# bh_ai8_di8_alph.net
KiCad netlist of a schematic drawn in Altium Designer
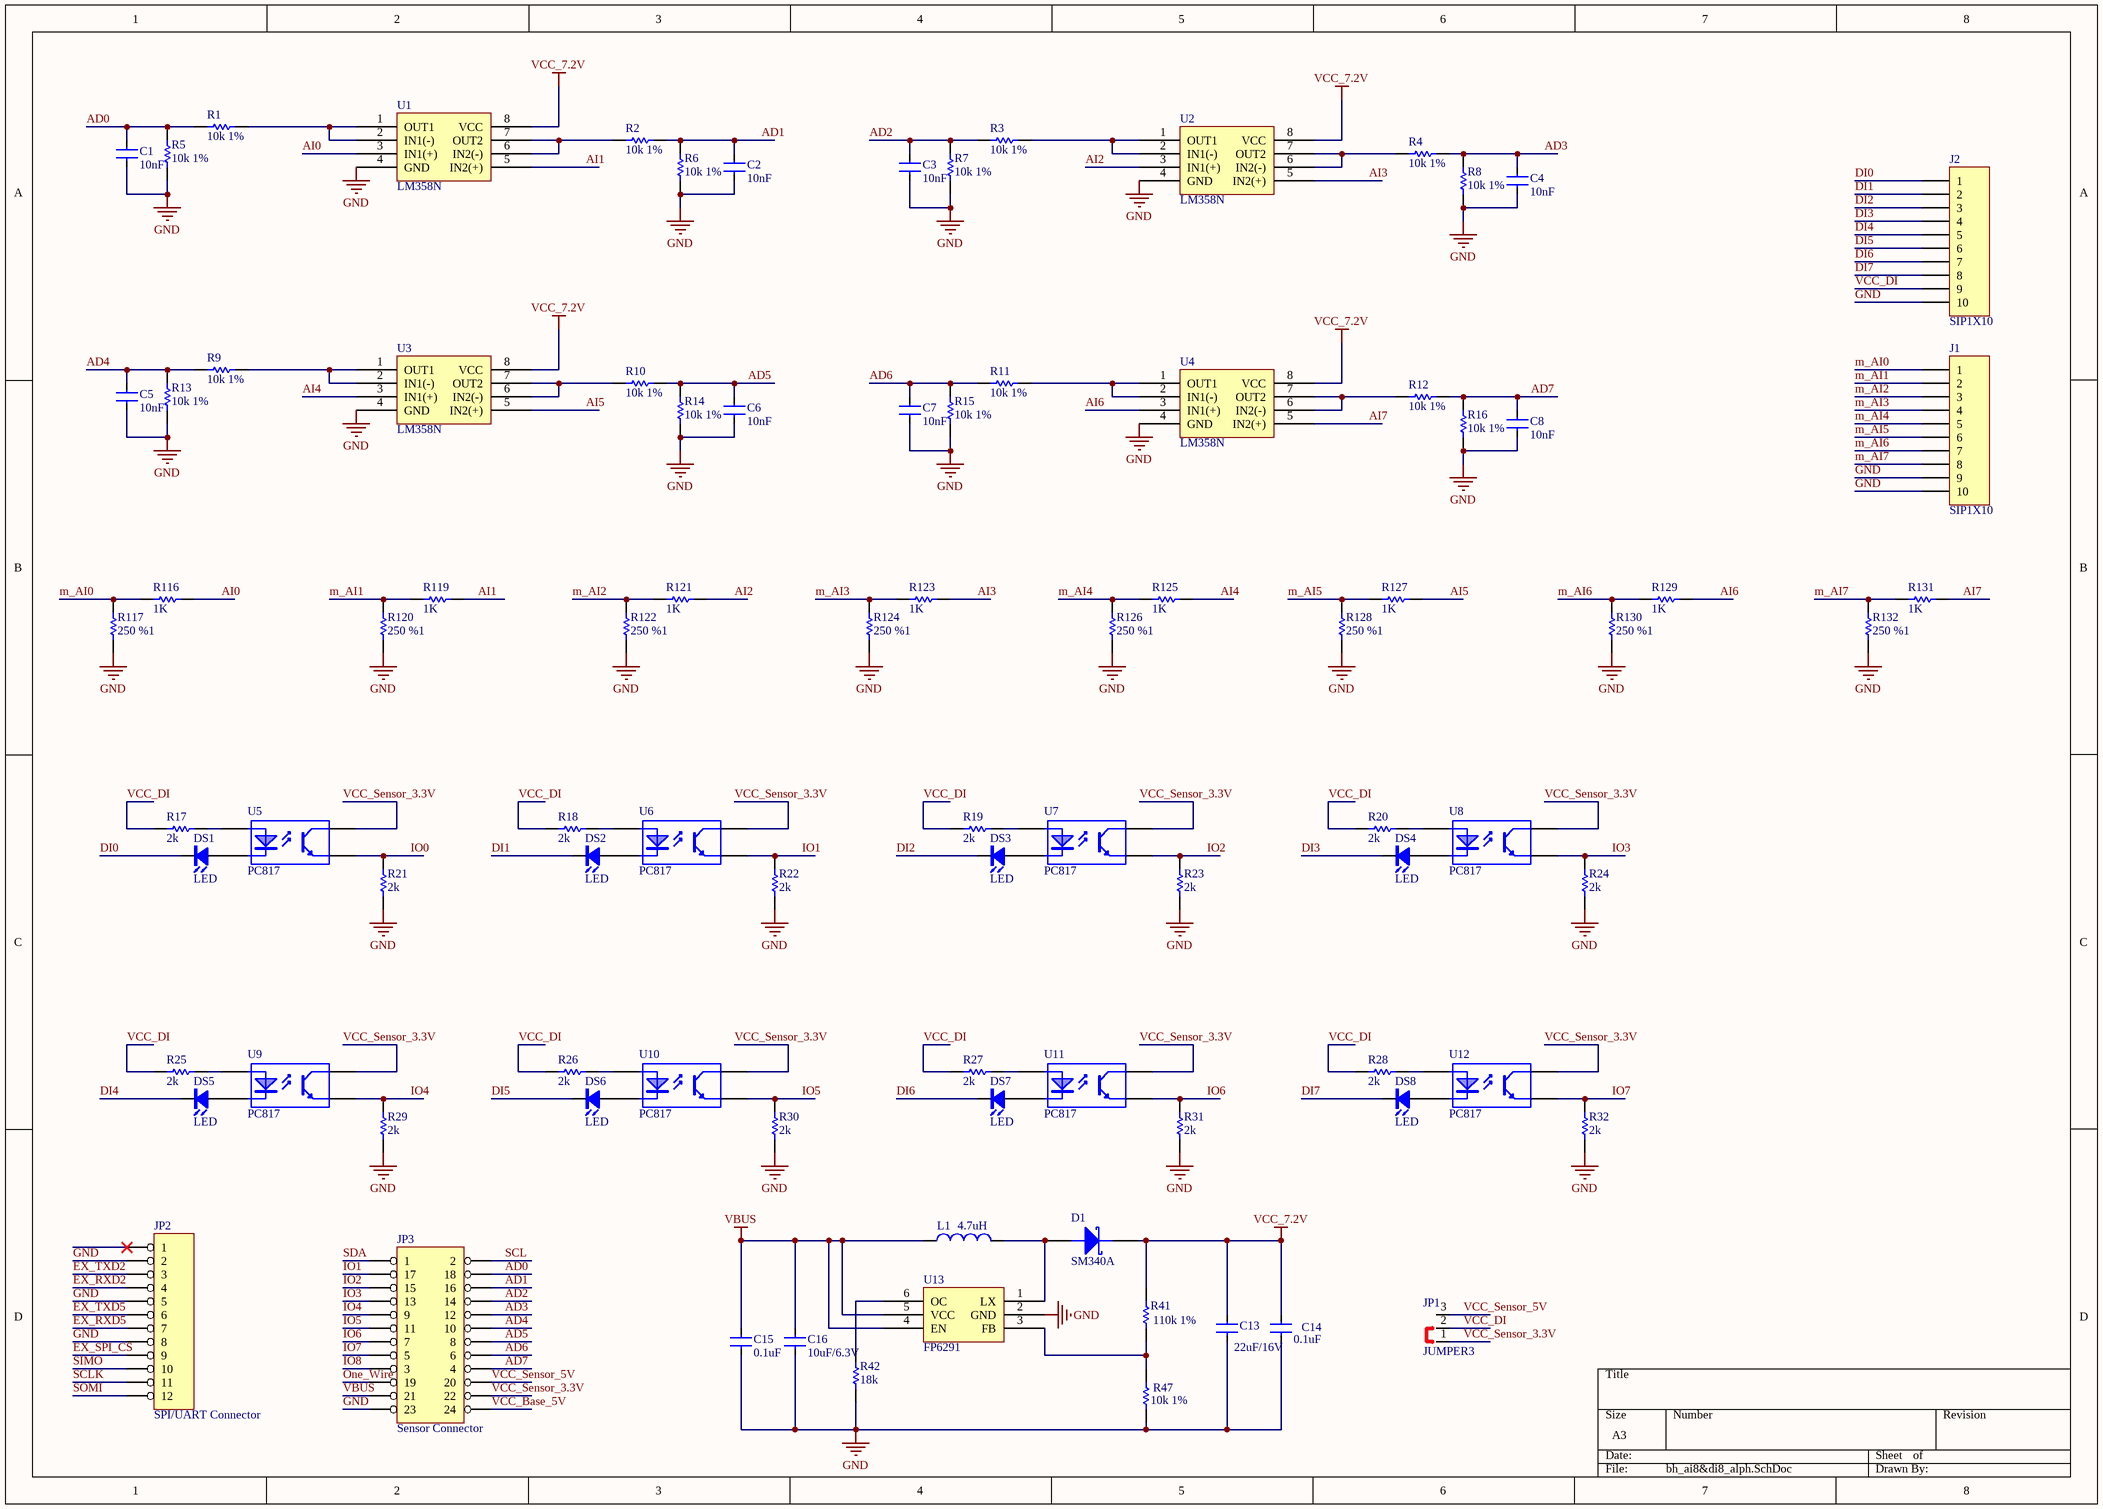
[diagram p0: bh_ai8&di8_alph.SchDoc]

(export (version "E")
  (design (tool "Eeschema 10.0.6"))
  (components
    (comp (ref "C1")
      (value "10nF")
      (footprint "C0603")
      (description "SMD-CAP")
      (libsource (lib "BH_DESIGN_DEVICE") (part "CAP-SMD"))
    )
    (comp (ref "C2")
      (value "10nF")
      (footprint "C0603")
      (description "SMD-CAP")
      (libsource (lib "BH_DESIGN_DEVICE") (part "CAP-SMD"))
    )
    (comp (ref "C3")
      (value "10nF")
      (footprint "C0603")
      (description "SMD-CAP")
      (libsource (lib "BH_DESIGN_DEVICE") (part "CAP-SMD"))
    )
    (comp (ref "C4")
      (value "10nF")
      (footprint "C0603")
      (description "SMD-CAP")
      (libsource (lib "BH_DESIGN_DEVICE") (part "CAP-SMD"))
    )
    (comp (ref "C5")
      (value "10nF")
      (footprint "C0603")
      (description "SMD-CAP")
      (libsource (lib "BH_DESIGN_DEVICE") (part "CAP-SMD"))
    )
    (comp (ref "C6")
      (value "10nF")
      (footprint "C0603")
      (description "SMD-CAP")
      (libsource (lib "BH_DESIGN_DEVICE") (part "CAP-SMD"))
    )
    (comp (ref "C7")
      (value "10nF")
      (footprint "C0603")
      (description "SMD-CAP")
      (libsource (lib "BH_DESIGN_DEVICE") (part "CAP-SMD"))
    )
    (comp (ref "C8")
      (value "10nF")
      (footprint "C0603")
      (description "SMD-CAP")
      (libsource (lib "BH_DESIGN_DEVICE") (part "CAP-SMD"))
    )
    (comp (ref "C13")
      (value "22uF/16V")
      (footprint "C0805")
      (description "SMD-CAP")
      (libsource (lib "5D_DEVICE") (part "CAP-SMD"))
    )
    (comp (ref "C14")
      (value "0.1uF")
      (footprint "C0603")
      (description "SMD-CAP")
      (libsource (lib "5D_DEVICE") (part "CAP-SMD"))
    )
    (comp (ref "C15")
      (value "0.1uF")
      (footprint "C0603")
      (description "SMD-CAP")
      (libsource (lib "5D_DEVICE") (part "CAP-SMD"))
    )
    (comp (ref "C16")
      (value "10uF/6.3V")
      (footprint "C0805")
      (description "SMD-CAP")
      (libsource (lib "5D_DEVICE") (part "CAP-SMD"))
    )
    (comp (ref "D1")
      (value "SM340A")
      (footprint "DO-214")
      (description "Schottky Diode")
      (libsource (lib "5D_DEVICE") (part "DIODE SCHOTTKY"))
    )
    (comp (ref "DS1") (value "LED") (footprint "D0805") (libsource (lib "BH_DESIGN_DEVICE") (part "LED")))
    (comp (ref "DS2") (value "LED") (footprint "D0805") (libsource (lib "BH_DESIGN_DEVICE") (part "LED")))
    (comp (ref "DS3") (value "LED") (footprint "D0805") (libsource (lib "BH_DESIGN_DEVICE") (part "LED")))
    (comp (ref "DS4") (value "LED") (footprint "D0805") (libsource (lib "BH_DESIGN_DEVICE") (part "LED")))
    (comp (ref "DS5") (value "LED") (footprint "D0805") (libsource (lib "BH_DESIGN_DEVICE") (part "LED")))
    (comp (ref "DS6") (value "LED") (footprint "D0805") (libsource (lib "BH_DESIGN_DEVICE") (part "LED")))
    (comp (ref "DS7") (value "LED") (footprint "D0805") (libsource (lib "BH_DESIGN_DEVICE") (part "LED")))
    (comp (ref "DS8") (value "LED") (footprint "D0805") (libsource (lib "BH_DESIGN_DEVICE") (part "LED")))
    (comp (ref "J1")
      (value "SIP1X10")
      (footprint "CON10*0.381")
      (description "Connector")
      (libsource (lib "BH_DESIGN_CONNECTOR") (part "SIP1X10"))
    )
    (comp (ref "J2")
      (value "SIP1X10")
      (footprint "CON10*0.381")
      (description "Connector")
      (libsource (lib "BH_DESIGN_CONNECTOR") (part "SIP1X10"))
    )
    (comp (ref "JP1")
      (value "JUMPER3")
      (footprint "SIP1X3X2.54")
      (description "Jumper")
      (libsource (lib "BH_DESIGN_CONNECTOR") (part "JUMPER3"))
    )
    (comp (ref "JP2")
      (value "SPI/UART Connector")
      (footprint "SIP1x12x2.54")
      (description "单排排针直角")
      (libsource (lib "5D_CONNECTOR") (part "SIP1X12"))
    )
    (comp (ref "JP3")
      (value "Sensor Connector")
      (footprint "SIP2X12X2.54")
      (description "双排排针直角")
      (libsource (lib "5D_CONNECTOR") (part "SIP2X12"))
    )
    (comp (ref "L1")
      (value "4.7uH")
      (footprint "R1206")
      (description "Inductor")
      (libsource (lib "5D_DEVICE") (part "INDUCTOR"))
    )
    (comp (ref "R1")
      (value "10k 1%")
      (footprint "R0603")
      (description "Resistor")
      (libsource (lib "BH_DESIGN_DEVICE") (part "RES"))
    )
    (comp (ref "R2")
      (value "10k 1%")
      (footprint "R0603")
      (description "Resistor")
      (libsource (lib "BH_DESIGN_DEVICE") (part "RES"))
    )
    (comp (ref "R3")
      (value "10k 1%")
      (footprint "R0603")
      (description "Resistor")
      (libsource (lib "BH_DESIGN_DEVICE") (part "RES"))
    )
    (comp (ref "R4")
      (value "10k 1%")
      (footprint "R0603")
      (description "Resistor")
      (libsource (lib "BH_DESIGN_DEVICE") (part "RES"))
    )
    (comp (ref "R5")
      (value "10k 1%")
      (footprint "R0603")
      (description "Resistor")
      (libsource (lib "BH_DESIGN_DEVICE") (part "RES"))
    )
    (comp (ref "R6")
      (value "10k 1%")
      (footprint "R0603")
      (description "Resistor")
      (libsource (lib "BH_DESIGN_DEVICE") (part "RES"))
    )
    (comp (ref "R7")
      (value "10k 1%")
      (footprint "R0603")
      (description "Resistor")
      (libsource (lib "BH_DESIGN_DEVICE") (part "RES"))
    )
    (comp (ref "R8")
      (value "10k 1%")
      (footprint "R0603")
      (description "Resistor")
      (libsource (lib "BH_DESIGN_DEVICE") (part "RES"))
    )
    (comp (ref "R9")
      (value "10k 1%")
      (footprint "R0603")
      (description "Resistor")
      (libsource (lib "BH_DESIGN_DEVICE") (part "RES"))
    )
    (comp (ref "R10")
      (value "10k 1%")
      (footprint "R0603")
      (description "Resistor")
      (libsource (lib "BH_DESIGN_DEVICE") (part "RES"))
    )
    (comp (ref "R11")
      (value "10k 1%")
      (footprint "R0603")
      (description "Resistor")
      (libsource (lib "BH_DESIGN_DEVICE") (part "RES"))
    )
    (comp (ref "R12")
      (value "10k 1%")
      (footprint "R0603")
      (description "Resistor")
      (libsource (lib "BH_DESIGN_DEVICE") (part "RES"))
    )
    (comp (ref "R13")
      (value "10k 1%")
      (footprint "R0603")
      (description "Resistor")
      (libsource (lib "BH_DESIGN_DEVICE") (part "RES"))
    )
    (comp (ref "R14")
      (value "10k 1%")
      (footprint "R0603")
      (description "Resistor")
      (libsource (lib "BH_DESIGN_DEVICE") (part "RES"))
    )
    (comp (ref "R15")
      (value "10k 1%")
      (footprint "R0603")
      (description "Resistor")
      (libsource (lib "BH_DESIGN_DEVICE") (part "RES"))
    )
    (comp (ref "R16")
      (value "10k 1%")
      (footprint "R0603")
      (description "Resistor")
      (libsource (lib "BH_DESIGN_DEVICE") (part "RES"))
    )
    (comp (ref "R17")
      (value "2k")
      (footprint "R0603")
      (description "Resistor")
      (libsource (lib "BH_DESIGN_DEVICE") (part "RES"))
    )
    (comp (ref "R18")
      (value "2k")
      (footprint "R0603")
      (description "Resistor")
      (libsource (lib "BH_DESIGN_DEVICE") (part "RES"))
    )
    (comp (ref "R19")
      (value "2k")
      (footprint "R0603")
      (description "Resistor")
      (libsource (lib "BH_DESIGN_DEVICE") (part "RES"))
    )
    (comp (ref "R20")
      (value "2k")
      (footprint "R0603")
      (description "Resistor")
      (libsource (lib "BH_DESIGN_DEVICE") (part "RES"))
    )
    (comp (ref "R21")
      (value "2k")
      (footprint "R0603")
      (description "Resistor")
      (libsource (lib "BH_DESIGN_DEVICE") (part "RES"))
    )
    (comp (ref "R22")
      (value "2k")
      (footprint "R0603")
      (description "Resistor")
      (libsource (lib "BH_DESIGN_DEVICE") (part "RES"))
    )
    (comp (ref "R23")
      (value "2k")
      (footprint "R0603")
      (description "Resistor")
      (libsource (lib "BH_DESIGN_DEVICE") (part "RES"))
    )
    (comp (ref "R24")
      (value "2k")
      (footprint "R0603")
      (description "Resistor")
      (libsource (lib "BH_DESIGN_DEVICE") (part "RES"))
    )
    (comp (ref "R25")
      (value "2k")
      (footprint "R0603")
      (description "Resistor")
      (libsource (lib "BH_DESIGN_DEVICE") (part "RES"))
    )
    (comp (ref "R26")
      (value "2k")
      (footprint "R0603")
      (description "Resistor")
      (libsource (lib "BH_DESIGN_DEVICE") (part "RES"))
    )
    (comp (ref "R27")
      (value "2k")
      (footprint "R0603")
      (description "Resistor")
      (libsource (lib "BH_DESIGN_DEVICE") (part "RES"))
    )
    (comp (ref "R28")
      (value "2k")
      (footprint "R0603")
      (description "Resistor")
      (libsource (lib "BH_DESIGN_DEVICE") (part "RES"))
    )
    (comp (ref "R29")
      (value "2k")
      (footprint "R0603")
      (description "Resistor")
      (libsource (lib "BH_DESIGN_DEVICE") (part "RES"))
    )
    (comp (ref "R30")
      (value "2k")
      (footprint "R0603")
      (description "Resistor")
      (libsource (lib "BH_DESIGN_DEVICE") (part "RES"))
    )
    (comp (ref "R31")
      (value "2k")
      (footprint "R0603")
      (description "Resistor")
      (libsource (lib "BH_DESIGN_DEVICE") (part "RES"))
    )
    (comp (ref "R32")
      (value "2k")
      (footprint "R0603")
      (description "Resistor")
      (libsource (lib "BH_DESIGN_DEVICE") (part "RES"))
    )
    (comp (ref "R41")
      (value "110k 1%")
      (footprint "R0603")
      (description "Resistor")
      (libsource (lib "5D_DEVICE") (part "RES"))
    )
    (comp (ref "R42")
      (value "18k")
      (footprint "R0603")
      (description "Resistor")
      (libsource (lib "5D_DEVICE") (part "RES"))
    )
    (comp (ref "R47")
      (value "10k 1%")
      (footprint "R0603")
      (description "Resistor")
      (libsource (lib "5D_DEVICE") (part "RES"))
    )
    (comp (ref "R116")
      (value "1K")
      (footprint "R0603")
      (description "Resistor")
      (libsource (lib "5D_DEVICE") (part "RES"))
    )
    (comp (ref "R117")
      (value "250 %1")
      (footprint "R0603")
      (description "Resistor")
      (libsource (lib "5D_DEVICE") (part "RES"))
    )
    (comp (ref "R119")
      (value "1K")
      (footprint "R0603")
      (description "Resistor")
      (libsource (lib "5D_DEVICE") (part "RES"))
    )
    (comp (ref "R120")
      (value "250 %1")
      (footprint "R0603")
      (description "Resistor")
      (libsource (lib "5D_DEVICE") (part "RES"))
    )
    (comp (ref "R121")
      (value "1K")
      (footprint "R0603")
      (description "Resistor")
      (libsource (lib "5D_DEVICE") (part "RES"))
    )
    (comp (ref "R122")
      (value "250 %1")
      (footprint "R0603")
      (description "Resistor")
      (libsource (lib "5D_DEVICE") (part "RES"))
    )
    (comp (ref "R123")
      (value "1K")
      (footprint "R0603")
      (description "Resistor")
      (libsource (lib "5D_DEVICE") (part "RES"))
    )
    (comp (ref "R124")
      (value "250 %1")
      (footprint "R0603")
      (description "Resistor")
      (libsource (lib "5D_DEVICE") (part "RES"))
    )
    (comp (ref "R125")
      (value "1K")
      (footprint "R0603")
      (description "Resistor")
      (libsource (lib "5D_DEVICE") (part "RES"))
    )
    (comp (ref "R126")
      (value "250 %1")
      (footprint "R0603")
      (description "Resistor")
      (libsource (lib "5D_DEVICE") (part "RES"))
    )
    (comp (ref "R127")
      (value "1K")
      (footprint "R0603")
      (description "Resistor")
      (libsource (lib "5D_DEVICE") (part "RES"))
    )
    (comp (ref "R128")
      (value "250 %1")
      (footprint "R0603")
      (description "Resistor")
      (libsource (lib "5D_DEVICE") (part "RES"))
    )
    (comp (ref "R129")
      (value "1K")
      (footprint "R0603")
      (description "Resistor")
      (libsource (lib "5D_DEVICE") (part "RES"))
    )
    (comp (ref "R130")
      (value "250 %1")
      (footprint "R0603")
      (description "Resistor")
      (libsource (lib "5D_DEVICE") (part "RES"))
    )
    (comp (ref "R131")
      (value "1K")
      (footprint "R0603")
      (description "Resistor")
      (libsource (lib "5D_DEVICE") (part "RES"))
    )
    (comp (ref "R132")
      (value "250 %1")
      (footprint "R0603")
      (description "Resistor")
      (libsource (lib "5D_DEVICE") (part "RES"))
    )
    (comp (ref "U1") (value "LM358N") (footprint "SO8NB") (libsource (lib "BH_DESIGN_IC") (part "LM358N")))
    (comp (ref "U2") (value "LM358N") (footprint "SO8NB") (libsource (lib "BH_DESIGN_IC") (part "LM358N")))
    (comp (ref "U3") (value "LM358N") (footprint "SO8NB") (libsource (lib "BH_DESIGN_IC") (part "LM358N")))
    (comp (ref "U4") (value "LM358N") (footprint "SO8NB") (libsource (lib "BH_DESIGN_IC") (part "LM358N")))
    (comp (ref "U5")
      (value "PC817")
      (footprint "SOP_4")
      (fields (field (name "PUBLISHER") "Altium Limited"))
      (libsource (lib "BH_DESIGN_DEVICE") (part "P521*1"))
    )
    (comp (ref "U6")
      (value "PC817")
      (footprint "SOP_4")
      (fields (field (name "PUBLISHER") "Altium Limited"))
      (libsource (lib "BH_DESIGN_DEVICE") (part "P521*1"))
    )
    (comp (ref "U7")
      (value "PC817")
      (footprint "SOP_4")
      (fields (field (name "PUBLISHER") "Altium Limited"))
      (libsource (lib "BH_DESIGN_DEVICE") (part "P521*1"))
    )
    (comp (ref "U8")
      (value "PC817")
      (footprint "SOP_4")
      (fields (field (name "PUBLISHER") "Altium Limited"))
      (libsource (lib "BH_DESIGN_DEVICE") (part "P521*1"))
    )
    (comp (ref "U9")
      (value "PC817")
      (footprint "SOP_4")
      (fields (field (name "PUBLISHER") "Altium Limited"))
      (libsource (lib "BH_DESIGN_DEVICE") (part "P521*1"))
    )
    (comp (ref "U10")
      (value "PC817")
      (footprint "SOP_4")
      (fields (field (name "PUBLISHER") "Altium Limited"))
      (libsource (lib "BH_DESIGN_DEVICE") (part "P521*1"))
    )
    (comp (ref "U11")
      (value "PC817")
      (footprint "SOP_4")
      (fields (field (name "PUBLISHER") "Altium Limited"))
      (libsource (lib "BH_DESIGN_DEVICE") (part "P521*1"))
    )
    (comp (ref "U12")
      (value "PC817")
      (footprint "SOP_4")
      (fields (field (name "PUBLISHER") "Altium Limited"))
      (libsource (lib "BH_DESIGN_DEVICE") (part "P521*1"))
    )
    (comp (ref "U13") (value "FP6291") (footprint "SOT23-6") (libsource (lib "5D_IC") (part "FP6291")))
  )
  (nets
    (net (code "1") (name "/AD0") (class "Default")
      (node (ref "C1") (pin "1") (pinfunction "1_1") (pintype "passive"))
      (node (ref "JP3") (pin "18") (pinfunction "18_18") (pintype "passive"))
      (node (ref "R1") (pin "2") (pinfunction "2_2") (pintype "passive"))
      (node (ref "R5") (pin "1") (pinfunction "1_1") (pintype "passive"))
    )
    (net (code "2") (name "/AD1") (class "Default")
      (node (ref "C2") (pin "1") (pinfunction "1_1") (pintype "passive"))
      (node (ref "JP3") (pin "16") (pinfunction "16_16") (pintype "passive"))
      (node (ref "R2") (pin "1") (pinfunction "1_1") (pintype "passive"))
      (node (ref "R6") (pin "1") (pinfunction "1_1") (pintype "passive"))
    )
    (net (code "3") (name "/AD2") (class "Default")
      (node (ref "C3") (pin "1") (pinfunction "1_1") (pintype "passive"))
      (node (ref "JP3") (pin "14") (pinfunction "14_14") (pintype "passive"))
      (node (ref "R3") (pin "2") (pinfunction "2_2") (pintype "passive"))
      (node (ref "R7") (pin "1") (pinfunction "1_1") (pintype "passive"))
    )
    (net (code "4") (name "/AD3") (class "Default")
      (node (ref "C4") (pin "1") (pinfunction "1_1") (pintype "passive"))
      (node (ref "JP3") (pin "12") (pinfunction "12_12") (pintype "passive"))
      (node (ref "R4") (pin "1") (pinfunction "1_1") (pintype "passive"))
      (node (ref "R8") (pin "1") (pinfunction "1_1") (pintype "passive"))
    )
    (net (code "5") (name "/AD4") (class "Default")
      (node (ref "C5") (pin "1") (pinfunction "1_1") (pintype "passive"))
      (node (ref "JP3") (pin "10") (pinfunction "10_10") (pintype "passive"))
      (node (ref "R13") (pin "1") (pinfunction "1_1") (pintype "passive"))
      (node (ref "R9") (pin "2") (pinfunction "2_2") (pintype "passive"))
    )
    (net (code "6") (name "/AD5") (class "Default")
      (node (ref "C6") (pin "1") (pinfunction "1_1") (pintype "passive"))
      (node (ref "JP3") (pin "8") (pinfunction "8_8") (pintype "passive"))
      (node (ref "R10") (pin "1") (pinfunction "1_1") (pintype "passive"))
      (node (ref "R14") (pin "1") (pinfunction "1_1") (pintype "passive"))
    )
    (net (code "7") (name "/AD6") (class "Default")
      (node (ref "C7") (pin "1") (pinfunction "1_1") (pintype "passive"))
      (node (ref "JP3") (pin "6") (pinfunction "6_6") (pintype "passive"))
      (node (ref "R11") (pin "2") (pinfunction "2_2") (pintype "passive"))
      (node (ref "R15") (pin "1") (pinfunction "1_1") (pintype "passive"))
    )
    (net (code "8") (name "/AD7") (class "Default")
      (node (ref "C8") (pin "1") (pinfunction "1_1") (pintype "passive"))
      (node (ref "JP3") (pin "4") (pinfunction "4_4") (pintype "passive"))
      (node (ref "R12") (pin "1") (pinfunction "1_1") (pintype "passive"))
      (node (ref "R16") (pin "1") (pinfunction "1_1") (pintype "passive"))
    )
    (net (code "9") (name "/AI0") (class "Default")
      (node (ref "R116") (pin "1") (pinfunction "1_1") (pintype "passive"))
      (node (ref "U1") (pin "3") (pinfunction "IN1(+)_3") (pintype "passive"))
    )
    (net (code "10") (name "/AI1") (class "Default")
      (node (ref "R119") (pin "1") (pinfunction "1_1") (pintype "passive"))
      (node (ref "U1") (pin "5") (pinfunction "IN2(+)_5") (pintype "passive"))
    )
    (net (code "11") (name "/AI2") (class "Default")
      (node (ref "R121") (pin "1") (pinfunction "1_1") (pintype "passive"))
      (node (ref "U2") (pin "3") (pinfunction "IN1(+)_3") (pintype "passive"))
    )
    (net (code "12") (name "/AI3") (class "Default")
      (node (ref "R123") (pin "1") (pinfunction "1_1") (pintype "passive"))
      (node (ref "U2") (pin "5") (pinfunction "IN2(+)_5") (pintype "passive"))
    )
    (net (code "13") (name "/AI4") (class "Default")
      (node (ref "R125") (pin "1") (pinfunction "1_1") (pintype "passive"))
      (node (ref "U3") (pin "3") (pinfunction "IN1(+)_3") (pintype "passive"))
    )
    (net (code "14") (name "/AI5") (class "Default")
      (node (ref "R127") (pin "1") (pinfunction "1_1") (pintype "passive"))
      (node (ref "U3") (pin "5") (pinfunction "IN2(+)_5") (pintype "passive"))
    )
    (net (code "15") (name "/AI6") (class "Default")
      (node (ref "R129") (pin "1") (pinfunction "1_1") (pintype "passive"))
      (node (ref "U4") (pin "3") (pinfunction "IN1(+)_3") (pintype "passive"))
    )
    (net (code "16") (name "/AI7") (class "Default")
      (node (ref "R131") (pin "1") (pinfunction "1_1") (pintype "passive"))
      (node (ref "U4") (pin "5") (pinfunction "IN2(+)_5") (pintype "passive"))
    )
    (net (code "17") (name "/DI0") (class "Default")
      (node (ref "DS1") (pin "K") (pinfunction "2_K") (pintype "passive"))
      (node (ref "J2") (pin "1") (pinfunction "1_1") (pintype "passive"))
    )
    (net (code "18") (name "/DI1") (class "Default")
      (node (ref "DS2") (pin "K") (pinfunction "2_K") (pintype "passive"))
      (node (ref "J2") (pin "2") (pinfunction "2_2") (pintype "passive"))
    )
    (net (code "19") (name "/DI2") (class "Default")
      (node (ref "DS3") (pin "K") (pinfunction "2_K") (pintype "passive"))
      (node (ref "J2") (pin "3") (pinfunction "3_3") (pintype "passive"))
    )
    (net (code "20") (name "/DI3") (class "Default")
      (node (ref "DS4") (pin "K") (pinfunction "2_K") (pintype "passive"))
      (node (ref "J2") (pin "4") (pinfunction "4_4") (pintype "passive"))
    )
    (net (code "21") (name "/DI4") (class "Default")
      (node (ref "DS5") (pin "K") (pinfunction "2_K") (pintype "passive"))
      (node (ref "J2") (pin "5") (pinfunction "5_5") (pintype "passive"))
    )
    (net (code "22") (name "/DI5") (class "Default")
      (node (ref "DS6") (pin "K") (pinfunction "2_K") (pintype "passive"))
      (node (ref "J2") (pin "6") (pinfunction "6_6") (pintype "passive"))
    )
    (net (code "23") (name "/DI6") (class "Default")
      (node (ref "DS7") (pin "K") (pinfunction "2_K") (pintype "passive"))
      (node (ref "J2") (pin "7") (pinfunction "7_7") (pintype "passive"))
    )
    (net (code "24") (name "/DI7") (class "Default")
      (node (ref "DS8") (pin "K") (pinfunction "2_K") (pintype "passive"))
      (node (ref "J2") (pin "8") (pinfunction "8_8") (pintype "passive"))
    )
    (net (code "25") (name "/EX_RXD2") (class "Default")
      (node (ref "JP2") (pin "4") (pinfunction "4_4") (pintype "passive"))
    )
    (net (code "26") (name "/EX_RXD5") (class "Default")
      (node (ref "JP2") (pin "7") (pinfunction "7_7") (pintype "passive"))
    )
    (net (code "27") (name "/EX_SPI_CS") (class "Default")
      (node (ref "JP2") (pin "9") (pinfunction "9_9") (pintype "passive"))
    )
    (net (code "28") (name "/EX_TXD2") (class "Default")
      (node (ref "JP2") (pin "3") (pinfunction "3_3") (pintype "passive"))
    )
    (net (code "29") (name "/EX_TXD5") (class "Default")
      (node (ref "JP2") (pin "6") (pinfunction "6_6") (pintype "passive"))
    )
    (net (code "30") (name "/IO0") (class "Default")
      (node (ref "R21") (pin "1") (pinfunction "1_1") (pintype "passive"))
      (node (ref "U5") (pin "3") (pinfunction "E_3") (pintype "passive"))
    )
    (net (code "31") (name "/IO1") (class "Default")
      (node (ref "JP3") (pin "17") (pinfunction "17_17") (pintype "passive"))
      (node (ref "R22") (pin "1") (pinfunction "1_1") (pintype "passive"))
      (node (ref "U6") (pin "3") (pinfunction "E_3") (pintype "passive"))
    )
    (net (code "32") (name "/IO2") (class "Default")
      (node (ref "JP3") (pin "15") (pinfunction "15_15") (pintype "passive"))
      (node (ref "R23") (pin "1") (pinfunction "1_1") (pintype "passive"))
      (node (ref "U7") (pin "3") (pinfunction "E_3") (pintype "passive"))
    )
    (net (code "33") (name "/IO3") (class "Default")
      (node (ref "JP3") (pin "13") (pinfunction "13_13") (pintype "passive"))
      (node (ref "R24") (pin "1") (pinfunction "1_1") (pintype "passive"))
      (node (ref "U8") (pin "3") (pinfunction "E_3") (pintype "passive"))
    )
    (net (code "34") (name "/IO4") (class "Default")
      (node (ref "JP3") (pin "9") (pinfunction "9_9") (pintype "passive"))
      (node (ref "R29") (pin "1") (pinfunction "1_1") (pintype "passive"))
      (node (ref "U9") (pin "3") (pinfunction "E_3") (pintype "passive"))
    )
    (net (code "35") (name "/IO5") (class "Default")
      (node (ref "JP3") (pin "11") (pinfunction "11_11") (pintype "passive"))
      (node (ref "R30") (pin "1") (pinfunction "1_1") (pintype "passive"))
      (node (ref "U10") (pin "3") (pinfunction "E_3") (pintype "passive"))
    )
    (net (code "36") (name "/IO6") (class "Default")
      (node (ref "JP3") (pin "7") (pinfunction "7_7") (pintype "passive"))
      (node (ref "R31") (pin "1") (pinfunction "1_1") (pintype "passive"))
      (node (ref "U11") (pin "3") (pinfunction "E_3") (pintype "passive"))
    )
    (net (code "37") (name "/IO7") (class "Default")
      (node (ref "JP3") (pin "5") (pinfunction "5_5") (pintype "passive"))
      (node (ref "R32") (pin "1") (pinfunction "1_1") (pintype "passive"))
      (node (ref "U12") (pin "3") (pinfunction "E_3") (pintype "passive"))
    )
    (net (code "38") (name "/IO8") (class "Default")
      (node (ref "JP3") (pin "3") (pinfunction "3_3") (pintype "passive"))
    )
    (net (code "39") (name "/One_Wire") (class "Default")
      (node (ref "JP3") (pin "19") (pinfunction "19_19") (pintype "passive"))
    )
    (net (code "40") (name "/SCL") (class "Default")
      (node (ref "JP3") (pin "2") (pinfunction "2_2") (pintype "passive"))
    )
    (net (code "41") (name "/SCLK") (class "Default")
      (node (ref "JP2") (pin "11") (pinfunction "11_11") (pintype "passive"))
    )
    (net (code "42") (name "/SDA") (class "Default")
      (node (ref "JP3") (pin "1") (pinfunction "1_1") (pintype "passive"))
    )
    (net (code "43") (name "/SIMO") (class "Default")
      (node (ref "JP2") (pin "10") (pinfunction "10_10") (pintype "passive"))
    )
    (net (code "44") (name "/SOMI") (class "Default")
      (node (ref "JP2") (pin "12") (pinfunction "12_12") (pintype "passive"))
    )
    (net (code "45") (name "/VCC_Base_5V") (class "Default")
      (node (ref "JP3") (pin "24") (pinfunction "24_24") (pintype "passive"))
    )
    (net (code "46") (name "/VCC_DI") (class "Default")
      (node (ref "J2") (pin "9") (pinfunction "9_9") (pintype "passive"))
      (node (ref "JP1") (pin "2") (pinfunction "2_2") (pintype "passive"))
      (node (ref "R17") (pin "2") (pinfunction "2_2") (pintype "passive"))
      (node (ref "R18") (pin "2") (pinfunction "2_2") (pintype "passive"))
      (node (ref "R19") (pin "2") (pinfunction "2_2") (pintype "passive"))
      (node (ref "R20") (pin "2") (pinfunction "2_2") (pintype "passive"))
      (node (ref "R25") (pin "2") (pinfunction "2_2") (pintype "passive"))
      (node (ref "R26") (pin "2") (pinfunction "2_2") (pintype "passive"))
      (node (ref "R27") (pin "2") (pinfunction "2_2") (pintype "passive"))
      (node (ref "R28") (pin "2") (pinfunction "2_2") (pintype "passive"))
    )
    (net (code "47") (name "/VCC_Sensor_3.3V") (class "Default")
      (node (ref "JP1") (pin "1") (pinfunction "1_1") (pintype "passive"))
      (node (ref "JP3") (pin "22") (pinfunction "22_22") (pintype "passive"))
      (node (ref "U10") (pin "4") (pinfunction "C_4") (pintype "passive"))
      (node (ref "U11") (pin "4") (pinfunction "C_4") (pintype "passive"))
      (node (ref "U12") (pin "4") (pinfunction "C_4") (pintype "passive"))
      (node (ref "U5") (pin "4") (pinfunction "C_4") (pintype "passive"))
      (node (ref "U6") (pin "4") (pinfunction "C_4") (pintype "passive"))
      (node (ref "U7") (pin "4") (pinfunction "C_4") (pintype "passive"))
      (node (ref "U8") (pin "4") (pinfunction "C_4") (pintype "passive"))
      (node (ref "U9") (pin "4") (pinfunction "C_4") (pintype "passive"))
    )
    (net (code "48") (name "/VCC_Sensor_5V") (class "Default")
      (node (ref "JP1") (pin "3") (pinfunction "3_3") (pintype "passive"))
      (node (ref "JP3") (pin "20") (pinfunction "20_20") (pintype "passive"))
    )
    (net (code "49") (name "/m_AI0") (class "Default")
      (node (ref "J1") (pin "1") (pinfunction "1_1") (pintype "passive"))
      (node (ref "R116") (pin "2") (pinfunction "2_2") (pintype "passive"))
      (node (ref "R117") (pin "1") (pinfunction "1_1") (pintype "passive"))
    )
    (net (code "50") (name "/m_AI1") (class "Default")
      (node (ref "J1") (pin "2") (pinfunction "2_2") (pintype "passive"))
      (node (ref "R119") (pin "2") (pinfunction "2_2") (pintype "passive"))
      (node (ref "R120") (pin "1") (pinfunction "1_1") (pintype "passive"))
    )
    (net (code "51") (name "/m_AI2") (class "Default")
      (node (ref "J1") (pin "3") (pinfunction "3_3") (pintype "passive"))
      (node (ref "R121") (pin "2") (pinfunction "2_2") (pintype "passive"))
      (node (ref "R122") (pin "1") (pinfunction "1_1") (pintype "passive"))
    )
    (net (code "52") (name "/m_AI3") (class "Default")
      (node (ref "J1") (pin "4") (pinfunction "4_4") (pintype "passive"))
      (node (ref "R123") (pin "2") (pinfunction "2_2") (pintype "passive"))
      (node (ref "R124") (pin "1") (pinfunction "1_1") (pintype "passive"))
    )
    (net (code "53") (name "/m_AI4") (class "Default")
      (node (ref "J1") (pin "5") (pinfunction "5_5") (pintype "passive"))
      (node (ref "R125") (pin "2") (pinfunction "2_2") (pintype "passive"))
      (node (ref "R126") (pin "1") (pinfunction "1_1") (pintype "passive"))
    )
    (net (code "54") (name "/m_AI5") (class "Default")
      (node (ref "J1") (pin "6") (pinfunction "6_6") (pintype "passive"))
      (node (ref "R127") (pin "2") (pinfunction "2_2") (pintype "passive"))
      (node (ref "R128") (pin "1") (pinfunction "1_1") (pintype "passive"))
    )
    (net (code "55") (name "/m_AI6") (class "Default")
      (node (ref "J1") (pin "7") (pinfunction "7_7") (pintype "passive"))
      (node (ref "R129") (pin "2") (pinfunction "2_2") (pintype "passive"))
      (node (ref "R130") (pin "1") (pinfunction "1_1") (pintype "passive"))
    )
    (net (code "56") (name "/m_AI7") (class "Default")
      (node (ref "J1") (pin "8") (pinfunction "8_8") (pintype "passive"))
      (node (ref "R131") (pin "2") (pinfunction "2_2") (pintype "passive"))
      (node (ref "R132") (pin "1") (pinfunction "1_1") (pintype "passive"))
    )
    (net (code "57") (name "GND") (class "Default")
      (node (ref "C1") (pin "2") (pinfunction "2_2") (pintype "passive"))
      (node (ref "C13") (pin "2") (pinfunction "2_2") (pintype "passive"))
      (node (ref "C14") (pin "2") (pinfunction "2_2") (pintype "passive"))
      (node (ref "C15") (pin "2") (pinfunction "2_2") (pintype "passive"))
      (node (ref "C16") (pin "2") (pinfunction "2_2") (pintype "passive"))
      (node (ref "C2") (pin "2") (pinfunction "2_2") (pintype "passive"))
      (node (ref "C3") (pin "2") (pinfunction "2_2") (pintype "passive"))
      (node (ref "C4") (pin "2") (pinfunction "2_2") (pintype "passive"))
      (node (ref "C5") (pin "2") (pinfunction "2_2") (pintype "passive"))
      (node (ref "C6") (pin "2") (pinfunction "2_2") (pintype "passive"))
      (node (ref "C7") (pin "2") (pinfunction "2_2") (pintype "passive"))
      (node (ref "C8") (pin "2") (pinfunction "2_2") (pintype "passive"))
      (node (ref "J1") (pin "10") (pinfunction "10_10") (pintype "passive"))
      (node (ref "J1") (pin "9") (pinfunction "9_9") (pintype "passive"))
      (node (ref "J2") (pin "10") (pinfunction "10_10") (pintype "passive"))
      (node (ref "JP2") (pin "2") (pinfunction "2_2") (pintype "passive"))
      (node (ref "JP2") (pin "5") (pinfunction "5_5") (pintype "passive"))
      (node (ref "JP2") (pin "8") (pinfunction "8_8") (pintype "passive"))
      (node (ref "JP3") (pin "23") (pinfunction "23_23") (pintype "passive"))
      (node (ref "R117") (pin "2") (pinfunction "2_2") (pintype "passive"))
      (node (ref "R120") (pin "2") (pinfunction "2_2") (pintype "passive"))
      (node (ref "R122") (pin "2") (pinfunction "2_2") (pintype "passive"))
      (node (ref "R124") (pin "2") (pinfunction "2_2") (pintype "passive"))
      (node (ref "R126") (pin "2") (pinfunction "2_2") (pintype "passive"))
      (node (ref "R128") (pin "2") (pinfunction "2_2") (pintype "passive"))
      (node (ref "R13") (pin "2") (pinfunction "2_2") (pintype "passive"))
      (node (ref "R130") (pin "2") (pinfunction "2_2") (pintype "passive"))
      (node (ref "R132") (pin "2") (pinfunction "2_2") (pintype "passive"))
      (node (ref "R14") (pin "2") (pinfunction "2_2") (pintype "passive"))
      (node (ref "R15") (pin "2") (pinfunction "2_2") (pintype "passive"))
      (node (ref "R16") (pin "2") (pinfunction "2_2") (pintype "passive"))
      (node (ref "R21") (pin "2") (pinfunction "2_2") (pintype "passive"))
      (node (ref "R22") (pin "2") (pinfunction "2_2") (pintype "passive"))
      (node (ref "R23") (pin "2") (pinfunction "2_2") (pintype "passive"))
      (node (ref "R24") (pin "2") (pinfunction "2_2") (pintype "passive"))
      (node (ref "R29") (pin "2") (pinfunction "2_2") (pintype "passive"))
      (node (ref "R30") (pin "2") (pinfunction "2_2") (pintype "passive"))
      (node (ref "R31") (pin "2") (pinfunction "2_2") (pintype "passive"))
      (node (ref "R32") (pin "2") (pinfunction "2_2") (pintype "passive"))
      (node (ref "R42") (pin "1") (pinfunction "1_1") (pintype "passive"))
      (node (ref "R47") (pin "1") (pinfunction "1_1") (pintype "passive"))
      (node (ref "R5") (pin "2") (pinfunction "2_2") (pintype "passive"))
      (node (ref "R6") (pin "2") (pinfunction "2_2") (pintype "passive"))
      (node (ref "R7") (pin "2") (pinfunction "2_2") (pintype "passive"))
      (node (ref "R8") (pin "2") (pinfunction "2_2") (pintype "passive"))
      (node (ref "U1") (pin "4") (pinfunction "GND_4") (pintype "passive"))
      (node (ref "U13") (pin "2") (pinfunction "GND_2") (pintype "passive"))
      (node (ref "U2") (pin "4") (pinfunction "GND_4") (pintype "passive"))
      (node (ref "U3") (pin "4") (pinfunction "GND_4") (pintype "passive"))
      (node (ref "U4") (pin "4") (pinfunction "GND_4") (pintype "passive"))
    )
    (net (code "58") (name "Net-(D1-A)") (class "Default")
      (node (ref "D1") (pin "1") (pinfunction "A_1") (pintype "passive"))
      (node (ref "L1") (pin "2") (pinfunction "2_2") (pintype "passive"))
      (node (ref "U13") (pin "1") (pinfunction "LX_1") (pintype "passive"))
    )
    (net (code "59") (name "Net-(DS1-1)") (class "Default")
      (node (ref "DS1") (pin "A") (pinfunction "1_A") (pintype "passive"))
      (node (ref "U5") (pin "2") (pinfunction "K_2") (pintype "passive"))
    )
    (net (code "60") (name "Net-(DS2-1)") (class "Default")
      (node (ref "DS2") (pin "A") (pinfunction "1_A") (pintype "passive"))
      (node (ref "U6") (pin "2") (pinfunction "K_2") (pintype "passive"))
    )
    (net (code "61") (name "Net-(DS3-1)") (class "Default")
      (node (ref "DS3") (pin "A") (pinfunction "1_A") (pintype "passive"))
      (node (ref "U7") (pin "2") (pinfunction "K_2") (pintype "passive"))
    )
    (net (code "62") (name "Net-(DS4-1)") (class "Default")
      (node (ref "DS4") (pin "A") (pinfunction "1_A") (pintype "passive"))
      (node (ref "U8") (pin "2") (pinfunction "K_2") (pintype "passive"))
    )
    (net (code "63") (name "Net-(DS5-1)") (class "Default")
      (node (ref "DS5") (pin "A") (pinfunction "1_A") (pintype "passive"))
      (node (ref "U9") (pin "2") (pinfunction "K_2") (pintype "passive"))
    )
    (net (code "64") (name "Net-(DS6-1)") (class "Default")
      (node (ref "DS6") (pin "A") (pinfunction "1_A") (pintype "passive"))
      (node (ref "U10") (pin "2") (pinfunction "K_2") (pintype "passive"))
    )
    (net (code "65") (name "Net-(DS7-1)") (class "Default")
      (node (ref "DS7") (pin "A") (pinfunction "1_A") (pintype "passive"))
      (node (ref "U11") (pin "2") (pinfunction "K_2") (pintype "passive"))
    )
    (net (code "66") (name "Net-(DS8-1)") (class "Default")
      (node (ref "DS8") (pin "A") (pinfunction "1_A") (pintype "passive"))
      (node (ref "U12") (pin "2") (pinfunction "K_2") (pintype "passive"))
    )
    (net (code "67") (name "Net-(U1-IN1(-))") (class "Default")
      (node (ref "R1") (pin "1") (pinfunction "1_1") (pintype "passive"))
      (node (ref "U1") (pin "1") (pinfunction "OUT1_1") (pintype "passive"))
      (node (ref "U1") (pin "2") (pinfunction "IN1(-)_2") (pintype "passive"))
    )
    (net (code "68") (name "Net-(U1-IN2(-))") (class "Default")
      (node (ref "R2") (pin "2") (pinfunction "2_2") (pintype "passive"))
      (node (ref "U1") (pin "6") (pinfunction "IN2(-)_6") (pintype "passive"))
      (node (ref "U1") (pin "7") (pinfunction "OUT2_7") (pintype "passive"))
    )
    (net (code "69") (name "Net-(U2-IN1(-))") (class "Default")
      (node (ref "R3") (pin "1") (pinfunction "1_1") (pintype "passive"))
      (node (ref "U2") (pin "1") (pinfunction "OUT1_1") (pintype "passive"))
      (node (ref "U2") (pin "2") (pinfunction "IN1(-)_2") (pintype "passive"))
    )
    (net (code "70") (name "Net-(U2-IN2(-))") (class "Default")
      (node (ref "R4") (pin "2") (pinfunction "2_2") (pintype "passive"))
      (node (ref "U2") (pin "6") (pinfunction "IN2(-)_6") (pintype "passive"))
      (node (ref "U2") (pin "7") (pinfunction "OUT2_7") (pintype "passive"))
    )
    (net (code "71") (name "Net-(U3-IN1(-))") (class "Default")
      (node (ref "R9") (pin "1") (pinfunction "1_1") (pintype "passive"))
      (node (ref "U3") (pin "1") (pinfunction "OUT1_1") (pintype "passive"))
      (node (ref "U3") (pin "2") (pinfunction "IN1(-)_2") (pintype "passive"))
    )
    (net (code "72") (name "Net-(U3-IN2(-))") (class "Default")
      (node (ref "R10") (pin "2") (pinfunction "2_2") (pintype "passive"))
      (node (ref "U3") (pin "6") (pinfunction "IN2(-)_6") (pintype "passive"))
      (node (ref "U3") (pin "7") (pinfunction "OUT2_7") (pintype "passive"))
    )
    (net (code "73") (name "Net-(U4-IN1(-))") (class "Default")
      (node (ref "R11") (pin "1") (pinfunction "1_1") (pintype "passive"))
      (node (ref "U4") (pin "1") (pinfunction "OUT1_1") (pintype "passive"))
      (node (ref "U4") (pin "2") (pinfunction "IN1(-)_2") (pintype "passive"))
    )
    (net (code "74") (name "Net-(U4-IN2(-))") (class "Default")
      (node (ref "R12") (pin "2") (pinfunction "2_2") (pintype "passive"))
      (node (ref "U4") (pin "6") (pinfunction "IN2(-)_6") (pintype "passive"))
      (node (ref "U4") (pin "7") (pinfunction "OUT2_7") (pintype "passive"))
    )
    (net (code "75") (name "Net-(U5-A)") (class "Default")
      (node (ref "R17") (pin "1") (pinfunction "1_1") (pintype "passive"))
      (node (ref "U5") (pin "1") (pinfunction "A_1") (pintype "passive"))
    )
    (net (code "76") (name "Net-(U6-A)") (class "Default")
      (node (ref "R18") (pin "1") (pinfunction "1_1") (pintype "passive"))
      (node (ref "U6") (pin "1") (pinfunction "A_1") (pintype "passive"))
    )
    (net (code "77") (name "Net-(U7-A)") (class "Default")
      (node (ref "R19") (pin "1") (pinfunction "1_1") (pintype "passive"))
      (node (ref "U7") (pin "1") (pinfunction "A_1") (pintype "passive"))
    )
    (net (code "78") (name "Net-(U8-A)") (class "Default")
      (node (ref "R20") (pin "1") (pinfunction "1_1") (pintype "passive"))
      (node (ref "U8") (pin "1") (pinfunction "A_1") (pintype "passive"))
    )
    (net (code "79") (name "Net-(U9-A)") (class "Default")
      (node (ref "R25") (pin "1") (pinfunction "1_1") (pintype "passive"))
      (node (ref "U9") (pin "1") (pinfunction "A_1") (pintype "passive"))
    )
    (net (code "80") (name "Net-(U10-A)") (class "Default")
      (node (ref "R26") (pin "1") (pinfunction "1_1") (pintype "passive"))
      (node (ref "U10") (pin "1") (pinfunction "A_1") (pintype "passive"))
    )
    (net (code "81") (name "Net-(U11-A)") (class "Default")
      (node (ref "R27") (pin "1") (pinfunction "1_1") (pintype "passive"))
      (node (ref "U11") (pin "1") (pinfunction "A_1") (pintype "passive"))
    )
    (net (code "82") (name "Net-(U12-A)") (class "Default")
      (node (ref "R28") (pin "1") (pinfunction "1_1") (pintype "passive"))
      (node (ref "U12") (pin "1") (pinfunction "A_1") (pintype "passive"))
    )
    (net (code "83") (name "Net-(U13-FB)") (class "Default")
      (node (ref "R41") (pin "1") (pinfunction "1_1") (pintype "passive"))
      (node (ref "R47") (pin "2") (pinfunction "2_2") (pintype "passive"))
      (node (ref "U13") (pin "3") (pinfunction "FB_3") (pintype "passive"))
    )
    (net (code "84") (name "Net-(U13-OC)") (class "Default")
      (node (ref "R42") (pin "2") (pinfunction "2_2") (pintype "passive"))
      (node (ref "U13") (pin "6") (pinfunction "OC_6") (pintype "passive"))
    )
    (net (code "85") (name "VBUS") (class "Default")
      (node (ref "C15") (pin "1") (pinfunction "1_1") (pintype "passive"))
      (node (ref "C16") (pin "1") (pinfunction "1_1") (pintype "passive"))
      (node (ref "JP3") (pin "21") (pinfunction "21_21") (pintype "passive"))
      (node (ref "L1") (pin "1") (pinfunction "1_1") (pintype "passive"))
      (node (ref "U13") (pin "4") (pinfunction "EN_4") (pintype "passive"))
      (node (ref "U13") (pin "5") (pinfunction "VCC_5") (pintype "passive"))
    )
    (net (code "86") (name "VCC_7.2V") (class "Default")
      (node (ref "C13") (pin "1") (pinfunction "1_1") (pintype "passive"))
      (node (ref "C14") (pin "1") (pinfunction "1_1") (pintype "passive"))
      (node (ref "D1") (pin "2") (pinfunction "K_2") (pintype "passive"))
      (node (ref "R41") (pin "2") (pinfunction "2_2") (pintype "passive"))
      (node (ref "U1") (pin "8") (pinfunction "VCC_8") (pintype "passive"))
      (node (ref "U2") (pin "8") (pinfunction "VCC_8") (pintype "passive"))
      (node (ref "U3") (pin "8") (pinfunction "VCC_8") (pintype "passive"))
      (node (ref "U4") (pin "8") (pinfunction "VCC_8") (pintype "passive"))
    )
    (net (code "87") (name "unconnected-(JP2-Pad1)") (class "Default")
      (node (ref "JP2") (pin "1") (pinfunction "1_1") (pintype "passive+no_connect"))
    )
  )
)
